# drums_01.net
KiCad netlist of a schematic drawn in EAGLE
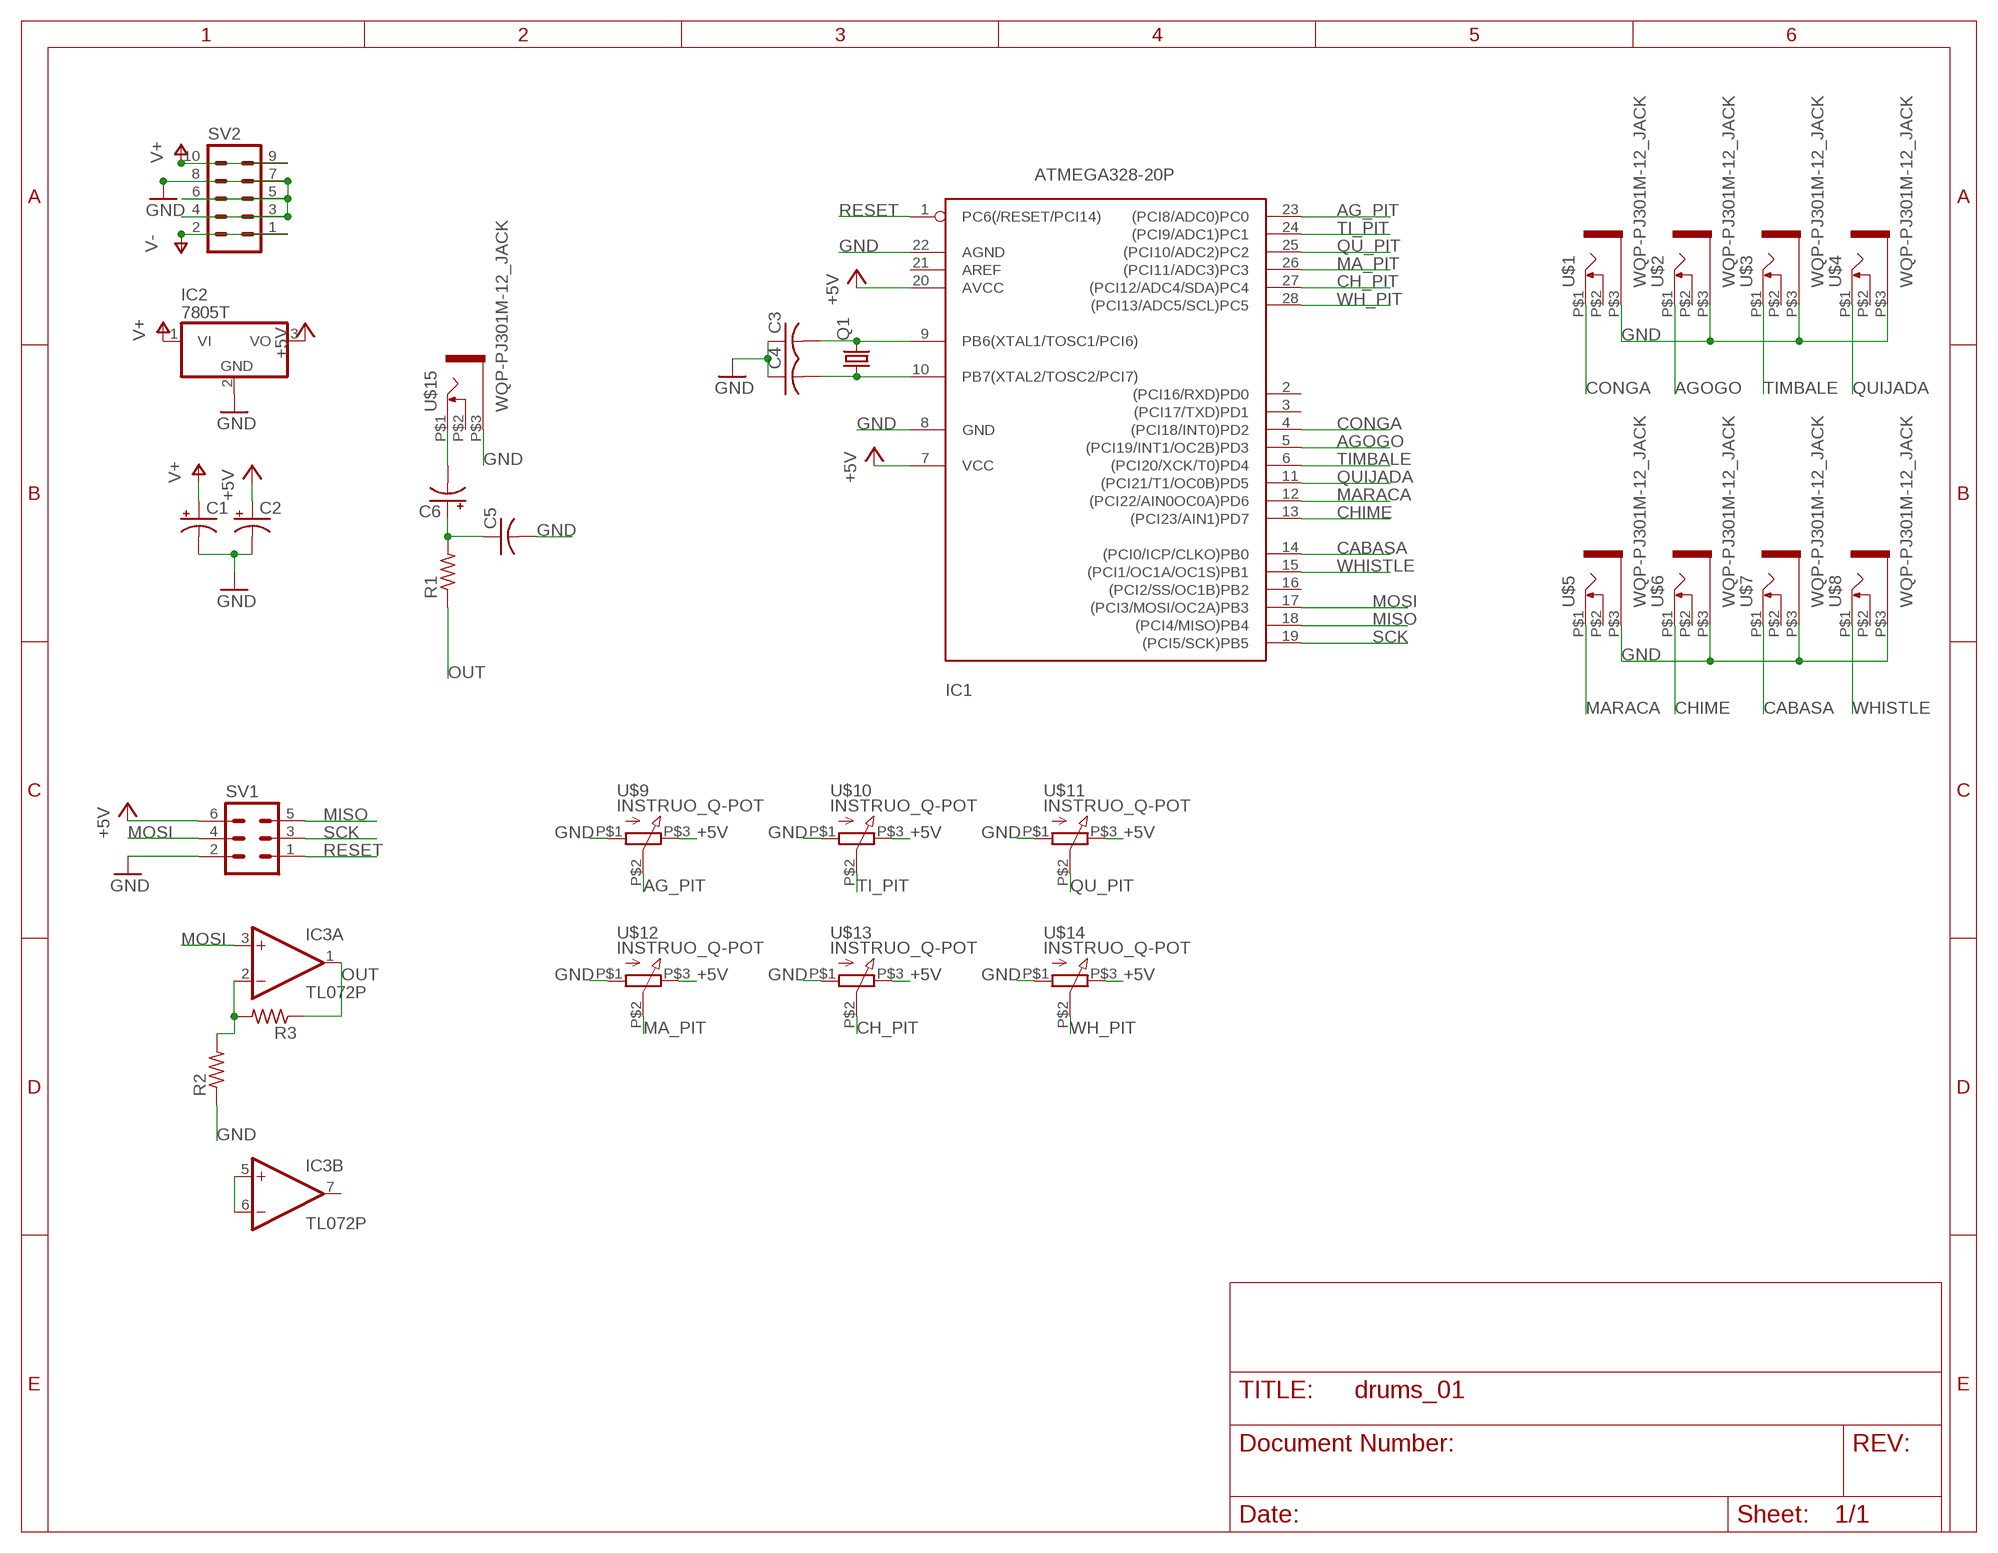
[diagram p0: schematic, sheet 1]

(export (version "E")
  (design (tool "Eeschema 10.0.6"))
  (components
    (comp (ref "C1")
      (value "CPOL-USE2.5-6")
      (footprint "eagle-import:E2,5-6")
      (libsource (lib "eagle-import") (part "CPOL-USE2.5-6"))
    )
    (comp (ref "C2")
      (value "CPOL-USE2.5-6")
      (footprint "eagle-import:E2,5-6")
      (libsource (lib "eagle-import") (part "CPOL-USE2.5-6"))
    )
    (comp (ref "C3")
      (value "C-US025-024X044")
      (footprint "eagle-import:C025-024X044")
      (libsource (lib "eagle-import") (part "C-US025-024X044"))
    )
    (comp (ref "C4")
      (value "C-US025-024X044")
      (footprint "eagle-import:C025-024X044")
      (libsource (lib "eagle-import") (part "C-US025-024X044"))
    )
    (comp (ref "C5")
      (value "C-US025-024X044")
      (footprint "eagle-import:C025-024X044")
      (libsource (lib "eagle-import") (part "C-US025-024X044"))
    )
    (comp (ref "C6")
      (value "CPOL-USE2.5-6")
      (footprint "eagle-import:E2,5-6")
      (libsource (lib "eagle-import") (part "CPOL-USE2.5-6"))
    )
    (comp (ref "IC1")
      (value "ATMEGA328-20P")
      (footprint "eagle-import:DIL28-3")
      (libsource (lib "eagle-import") (part "ATMEGA328P-20"))
    )
    (comp (ref "IC2")
      (value "7805T")
      (footprint "eagle-import:TO220H")
      (libsource (lib "eagle-import") (part "78T05"))
    )
    (comp (ref "IC3")
      (value "TL072P")
      (footprint "eagle-import:DIL08")
      (libsource (lib "eagle-import") (part "TL072P"))
    )
    (comp (ref "Q1")
      (value "CRYSTALHC49U-V")
      (footprint "eagle-import:HC49U-V")
      (libsource (lib "eagle-import") (part "CRYSTALHC49U-V"))
    )
    (comp (ref "R1")
      (value "R-US_0207/12")
      (footprint "eagle-import:0207_12")
      (libsource (lib "eagle-import") (part "R-US_0207/12"))
    )
    (comp (ref "R2")
      (value "R-US_0207/12")
      (footprint "eagle-import:0207_12")
      (libsource (lib "eagle-import") (part "R-US_0207/12"))
    )
    (comp (ref "R3")
      (value "R-US_0207/12")
      (footprint "eagle-import:0207_12")
      (libsource (lib "eagle-import") (part "R-US_0207/12"))
    )
    (comp (ref "SV1")
      (value "MA03-2")
      (footprint "eagle-import:MA03-2")
      (libsource (lib "eagle-import") (part "MA03-2"))
    )
    (comp (ref "SV2")
      (value "MA05-2")
      (footprint "eagle-import:MA05-2")
      (libsource (lib "eagle-import") (part "MA05-2"))
    )
    (comp (ref "U$1")
      (value "WQP-PJ301M-12_JACK")
      (footprint "eagle-import:WQP-PJ301M-12_JACK")
      (libsource (lib "eagle-import") (part "WQP-PJ301M-12_JACK"))
    )
    (comp (ref "U$2")
      (value "WQP-PJ301M-12_JACK")
      (footprint "eagle-import:WQP-PJ301M-12_JACK")
      (libsource (lib "eagle-import") (part "WQP-PJ301M-12_JACK"))
    )
    (comp (ref "U$3")
      (value "WQP-PJ301M-12_JACK")
      (footprint "eagle-import:WQP-PJ301M-12_JACK")
      (libsource (lib "eagle-import") (part "WQP-PJ301M-12_JACK"))
    )
    (comp (ref "U$4")
      (value "WQP-PJ301M-12_JACK")
      (footprint "eagle-import:WQP-PJ301M-12_JACK")
      (libsource (lib "eagle-import") (part "WQP-PJ301M-12_JACK"))
    )
    (comp (ref "U$5")
      (value "WQP-PJ301M-12_JACK")
      (footprint "eagle-import:WQP-PJ301M-12_JACK")
      (libsource (lib "eagle-import") (part "WQP-PJ301M-12_JACK"))
    )
    (comp (ref "U$6")
      (value "WQP-PJ301M-12_JACK")
      (footprint "eagle-import:WQP-PJ301M-12_JACK")
      (libsource (lib "eagle-import") (part "WQP-PJ301M-12_JACK"))
    )
    (comp (ref "U$7")
      (value "WQP-PJ301M-12_JACK")
      (footprint "eagle-import:WQP-PJ301M-12_JACK")
      (libsource (lib "eagle-import") (part "WQP-PJ301M-12_JACK"))
    )
    (comp (ref "U$8")
      (value "WQP-PJ301M-12_JACK")
      (footprint "eagle-import:WQP-PJ301M-12_JACK")
      (libsource (lib "eagle-import") (part "WQP-PJ301M-12_JACK"))
    )
    (comp (ref "U$9")
      (value "INSTRUO_Q-POT")
      (footprint "eagle-import:INSTRUO_Q-POT")
      (libsource (lib "eagle-import") (part "INSTRUO_Q-POT"))
    )
    (comp (ref "U$10")
      (value "INSTRUO_Q-POT")
      (footprint "eagle-import:INSTRUO_Q-POT")
      (libsource (lib "eagle-import") (part "INSTRUO_Q-POT"))
    )
    (comp (ref "U$11")
      (value "INSTRUO_Q-POT")
      (footprint "eagle-import:INSTRUO_Q-POT")
      (libsource (lib "eagle-import") (part "INSTRUO_Q-POT"))
    )
    (comp (ref "U$12")
      (value "INSTRUO_Q-POT")
      (footprint "eagle-import:INSTRUO_Q-POT")
      (libsource (lib "eagle-import") (part "INSTRUO_Q-POT"))
    )
    (comp (ref "U$13")
      (value "INSTRUO_Q-POT")
      (footprint "eagle-import:INSTRUO_Q-POT")
      (libsource (lib "eagle-import") (part "INSTRUO_Q-POT"))
    )
    (comp (ref "U$14")
      (value "INSTRUO_Q-POT")
      (footprint "eagle-import:INSTRUO_Q-POT")
      (libsource (lib "eagle-import") (part "INSTRUO_Q-POT"))
    )
    (comp (ref "U$15")
      (value "WQP-PJ301M-12_JACK")
      (footprint "eagle-import:WQP-PJ301M-12_JACK")
      (libsource (lib "eagle-import") (part "WQP-PJ301M-12_JACK"))
    )
  )
  (nets
    (net (code "1") (name "+5V") (class "Default")
      (node (ref "C2") (pin "+") (pinfunction "+_+") (pintype "passive"))
      (node (ref "IC1") (pin "20") (pinfunction "AVCC_20") (pintype "bidirectional"))
      (node (ref "IC1") (pin "7") (pinfunction "VCC_7") (pintype "bidirectional"))
      (node (ref "IC2") (pin "3") (pinfunction "VO_3") (pintype "passive"))
      (node (ref "SV1") (pin "6") (pinfunction "6_6") (pintype "passive"))
      (node (ref "U$10") (pin "P$3") (pinfunction "3_P$3") (pintype "passive"))
      (node (ref "U$11") (pin "P$3") (pinfunction "3_P$3") (pintype "passive"))
      (node (ref "U$12") (pin "P$3") (pinfunction "3_P$3") (pintype "passive"))
      (node (ref "U$13") (pin "P$3") (pinfunction "3_P$3") (pintype "passive"))
      (node (ref "U$14") (pin "P$3") (pinfunction "3_P$3") (pintype "passive"))
      (node (ref "U$9") (pin "P$3") (pinfunction "3_P$3") (pintype "passive"))
    )
    (net (code "2") (name "/AGOGO") (class "Default")
      (node (ref "IC1") (pin "5") (pinfunction "(PCI19/INT1/OC2B)PD3_5") (pintype "bidirectional"))
      (node (ref "U$2") (pin "P$1") (pinfunction "2_P$1") (pintype "passive"))
    )
    (net (code "3") (name "/AG_PIT") (class "Default")
      (node (ref "IC1") (pin "23") (pinfunction "(PCI8/ADC0)PC0_23") (pintype "bidirectional"))
      (node (ref "U$9") (pin "P$2") (pinfunction "2_P$2") (pintype "passive"))
    )
    (net (code "4") (name "/CABASA") (class "Default")
      (node (ref "IC1") (pin "14") (pinfunction "(PCI0/ICP/CLKO)PB0_14") (pintype "bidirectional"))
      (node (ref "U$7") (pin "P$1") (pinfunction "2_P$1") (pintype "passive"))
    )
    (net (code "5") (name "/CHIME") (class "Default")
      (node (ref "IC1") (pin "13") (pinfunction "(PCI23/AIN1)PD7_13") (pintype "bidirectional"))
      (node (ref "U$6") (pin "P$1") (pinfunction "2_P$1") (pintype "passive"))
    )
    (net (code "6") (name "/CH_PIT") (class "Default")
      (node (ref "IC1") (pin "27") (pinfunction "(PCI12/ADC4/SDA)PC4_27") (pintype "bidirectional"))
      (node (ref "U$13") (pin "P$2") (pinfunction "2_P$2") (pintype "passive"))
    )
    (net (code "7") (name "/CONGA") (class "Default")
      (node (ref "IC1") (pin "4") (pinfunction "(PCI18/INT0)PD2_4") (pintype "bidirectional"))
      (node (ref "U$1") (pin "P$1") (pinfunction "2_P$1") (pintype "passive"))
    )
    (net (code "8") (name "/MARACA") (class "Default")
      (node (ref "IC1") (pin "12") (pinfunction "(PCI22/AIN0OC0A)PD6_12") (pintype "bidirectional"))
      (node (ref "U$5") (pin "P$1") (pinfunction "2_P$1") (pintype "passive"))
    )
    (net (code "9") (name "/MA_PIT") (class "Default")
      (node (ref "IC1") (pin "26") (pinfunction "(PCI11/ADC3)PC3_26") (pintype "bidirectional"))
      (node (ref "U$12") (pin "P$2") (pinfunction "2_P$2") (pintype "passive"))
    )
    (net (code "10") (name "/MISO") (class "Default")
      (node (ref "IC1") (pin "18") (pinfunction "(PCI4/MISO)PB4_18") (pintype "bidirectional"))
      (node (ref "SV1") (pin "5") (pinfunction "5_5") (pintype "passive"))
    )
    (net (code "11") (name "/MOSI") (class "Default")
      (node (ref "IC1") (pin "17") (pinfunction "(PCI3/MOSI/OC2A)PB3_17") (pintype "bidirectional"))
      (node (ref "IC3") (pin "3") (pinfunction "+IN_3") (pintype "input"))
      (node (ref "SV1") (pin "4") (pinfunction "4_4") (pintype "passive"))
    )
    (net (code "12") (name "/OUT") (class "Default")
      (node (ref "IC3") (pin "1") (pinfunction "OUT_1") (pintype "output"))
      (node (ref "R1") (pin "1") (pinfunction "1_1") (pintype "passive"))
      (node (ref "R3") (pin "1") (pinfunction "1_1") (pintype "passive"))
    )
    (net (code "13") (name "/QUIJADA") (class "Default")
      (node (ref "IC1") (pin "11") (pinfunction "(PCI21/T1/OC0B)PD5_11") (pintype "bidirectional"))
      (node (ref "U$4") (pin "P$1") (pinfunction "2_P$1") (pintype "passive"))
    )
    (net (code "14") (name "/QU_PIT") (class "Default")
      (node (ref "IC1") (pin "25") (pinfunction "(PCI10/ADC2)PC2_25") (pintype "bidirectional"))
      (node (ref "U$11") (pin "P$2") (pinfunction "2_P$2") (pintype "passive"))
    )
    (net (code "15") (name "/RESET") (class "Default")
      (node (ref "IC1") (pin "1") (pinfunction "PC6(/RESET/PCI14)_1") (pintype "bidirectional"))
      (node (ref "SV1") (pin "1") (pinfunction "1_1") (pintype "passive"))
    )
    (net (code "16") (name "/SCK") (class "Default")
      (node (ref "IC1") (pin "19") (pinfunction "(PCI5/SCK)PB5_19") (pintype "bidirectional"))
      (node (ref "SV1") (pin "3") (pinfunction "3_3") (pintype "passive"))
    )
    (net (code "17") (name "/TIMBALE") (class "Default")
      (node (ref "IC1") (pin "6") (pinfunction "(PCI20/XCK/T0)PD4_6") (pintype "bidirectional"))
      (node (ref "U$3") (pin "P$1") (pinfunction "2_P$1") (pintype "passive"))
    )
    (net (code "18") (name "/TI_PIT") (class "Default")
      (node (ref "IC1") (pin "24") (pinfunction "(PCI9/ADC1)PC1_24") (pintype "bidirectional"))
      (node (ref "U$10") (pin "P$2") (pinfunction "2_P$2") (pintype "passive"))
    )
    (net (code "19") (name "/WHISTLE") (class "Default")
      (node (ref "IC1") (pin "15") (pinfunction "(PCI1/OC1A/OC1S)PB1_15") (pintype "bidirectional"))
      (node (ref "U$8") (pin "P$1") (pinfunction "2_P$1") (pintype "passive"))
    )
    (net (code "20") (name "/WH_PIT") (class "Default")
      (node (ref "IC1") (pin "28") (pinfunction "(PCI13/ADC5/SCL)PC5_28") (pintype "bidirectional"))
      (node (ref "U$14") (pin "P$2") (pinfunction "2_P$2") (pintype "passive"))
    )
    (net (code "21") (name "GND") (class "Default")
      (node (ref "C1") (pin "-") (pinfunction "-_-") (pintype "passive"))
      (node (ref "C2") (pin "-") (pinfunction "-_-") (pintype "passive"))
      (node (ref "C3") (pin "1") (pinfunction "1_1") (pintype "passive"))
      (node (ref "C4") (pin "1") (pinfunction "1_1") (pintype "passive"))
      (node (ref "C5") (pin "2") (pinfunction "2_2") (pintype "passive"))
      (node (ref "IC1") (pin "22") (pinfunction "AGND_22") (pintype "bidirectional"))
      (node (ref "IC1") (pin "8") (pinfunction "GND_8") (pintype "bidirectional"))
      (node (ref "IC2") (pin "2") (pinfunction "GND_2") (pintype "passive"))
      (node (ref "R2") (pin "1") (pinfunction "1_1") (pintype "passive"))
      (node (ref "SV1") (pin "2") (pinfunction "2_2") (pintype "passive"))
      (node (ref "SV2") (pin "3") (pinfunction "3_3") (pintype "passive"))
      (node (ref "SV2") (pin "4") (pinfunction "4_4") (pintype "passive"))
      (node (ref "SV2") (pin "5") (pinfunction "5_5") (pintype "passive"))
      (node (ref "SV2") (pin "6") (pinfunction "6_6") (pintype "passive"))
      (node (ref "SV2") (pin "7") (pinfunction "7_7") (pintype "passive"))
      (node (ref "SV2") (pin "8") (pinfunction "8_8") (pintype "passive"))
      (node (ref "U$1") (pin "P$3") (pinfunction "1_P$3") (pintype "passive"))
      (node (ref "U$10") (pin "P$1") (pinfunction "1_P$1") (pintype "passive"))
      (node (ref "U$11") (pin "P$1") (pinfunction "1_P$1") (pintype "passive"))
      (node (ref "U$12") (pin "P$1") (pinfunction "1_P$1") (pintype "passive"))
      (node (ref "U$13") (pin "P$1") (pinfunction "1_P$1") (pintype "passive"))
      (node (ref "U$14") (pin "P$1") (pinfunction "1_P$1") (pintype "passive"))
      (node (ref "U$15") (pin "P$3") (pinfunction "1_P$3") (pintype "passive"))
      (node (ref "U$2") (pin "P$3") (pinfunction "1_P$3") (pintype "passive"))
      (node (ref "U$3") (pin "P$3") (pinfunction "1_P$3") (pintype "passive"))
      (node (ref "U$4") (pin "P$3") (pinfunction "1_P$3") (pintype "passive"))
      (node (ref "U$5") (pin "P$3") (pinfunction "1_P$3") (pintype "passive"))
      (node (ref "U$6") (pin "P$3") (pinfunction "1_P$3") (pintype "passive"))
      (node (ref "U$7") (pin "P$3") (pinfunction "1_P$3") (pintype "passive"))
      (node (ref "U$8") (pin "P$3") (pinfunction "1_P$3") (pintype "passive"))
      (node (ref "U$9") (pin "P$1") (pinfunction "1_P$1") (pintype "passive"))
    )
    (net (code "22") (name "Net-(C5-Pad1)") (class "Default")
      (node (ref "C5") (pin "1") (pinfunction "1_1") (pintype "passive"))
      (node (ref "C6") (pin "+") (pinfunction "+_+") (pintype "passive"))
      (node (ref "R1") (pin "2") (pinfunction "2_2") (pintype "passive"))
    )
    (net (code "23") (name "Net-(IC1-PB6(XTAL1{slash}TOSC1{slash}PCI6))") (class "Default")
      (node (ref "C3") (pin "2") (pinfunction "2_2") (pintype "passive"))
      (node (ref "IC1") (pin "9") (pinfunction "PB6(XTAL1/TOSC1/PCI6)_9") (pintype "bidirectional"))
      (node (ref "Q1") (pin "2") (pinfunction "2_2") (pintype "passive"))
    )
    (net (code "24") (name "Net-(IC1-PB7(XTAL2{slash}TOSC2{slash}PCI7))") (class "Default")
      (node (ref "C4") (pin "2") (pinfunction "2_2") (pintype "passive"))
      (node (ref "IC1") (pin "10") (pinfunction "PB7(XTAL2/TOSC2/PCI7)_10") (pintype "bidirectional"))
      (node (ref "Q1") (pin "1") (pinfunction "1_1") (pintype "passive"))
    )
    (net (code "25") (name "Net-(IC3A--IN)") (class "Default")
      (node (ref "IC3") (pin "2") (pinfunction "-IN_2") (pintype "input"))
      (node (ref "R2") (pin "2") (pinfunction "2_2") (pintype "passive"))
      (node (ref "R3") (pin "2") (pinfunction "2_2") (pintype "passive"))
    )
    (net (code "26") (name "Net-(IC3B-+IN)") (class "Default")
      (node (ref "IC3") (pin "5") (pinfunction "+IN_5") (pintype "input"))
      (node (ref "IC3") (pin "6") (pinfunction "-IN_6") (pintype "input"))
    )
    (net (code "27") (name "Net-(U$15-2)") (class "Default")
      (node (ref "C6") (pin "-") (pinfunction "-_-") (pintype "passive"))
      (node (ref "U$15") (pin "P$1") (pinfunction "2_P$1") (pintype "passive"))
    )
    (net (code "28") (name "V+") (class "Default")
      (node (ref "C1") (pin "+") (pinfunction "+_+") (pintype "passive"))
      (node (ref "IC2") (pin "1") (pinfunction "VI_1") (pintype "input"))
      (node (ref "SV2") (pin "10") (pinfunction "10_10") (pintype "passive"))
      (node (ref "SV2") (pin "9") (pinfunction "9_9") (pintype "passive"))
    )
    (net (code "29") (name "V-") (class "Default")
      (node (ref "SV2") (pin "1") (pinfunction "1_1") (pintype "passive"))
      (node (ref "SV2") (pin "2") (pinfunction "2_2") (pintype "passive"))
    )
    (net (code "30") (name "unconnected-(IC1-(PCI2{slash}SS{slash}OC1B)PB2-Pad16)") (class "Default")
      (node (ref "IC1") (pin "16") (pinfunction "(PCI2/SS/OC1B)PB2_16") (pintype "bidirectional"))
    )
    (net (code "31") (name "unconnected-(IC1-(PCI16{slash}RXD)PD0-Pad2)") (class "Default")
      (node (ref "IC1") (pin "2") (pinfunction "(PCI16/RXD)PD0_2") (pintype "bidirectional"))
    )
    (net (code "32") (name "unconnected-(IC1-(PCI17{slash}TXD)PD1-Pad3)") (class "Default")
      (node (ref "IC1") (pin "3") (pinfunction "(PCI17/TXD)PD1_3") (pintype "bidirectional"))
    )
    (net (code "33") (name "unconnected-(IC1-AREF-Pad21)") (class "Default")
      (node (ref "IC1") (pin "21") (pinfunction "AREF_21") (pintype "bidirectional"))
    )
    (net (code "34") (name "unconnected-(IC3B-OUT-Pad7)") (class "Default")
      (node (ref "IC3") (pin "7") (pinfunction "OUT_7") (pintype "output"))
    )
    (net (code "35") (name "unconnected-(U$1-3-PadP$2)") (class "Default")
      (node (ref "U$1") (pin "P$2") (pinfunction "3_P$2") (pintype "passive"))
    )
    (net (code "36") (name "unconnected-(U$2-3-PadP$2)") (class "Default")
      (node (ref "U$2") (pin "P$2") (pinfunction "3_P$2") (pintype "passive"))
    )
    (net (code "37") (name "unconnected-(U$3-3-PadP$2)") (class "Default")
      (node (ref "U$3") (pin "P$2") (pinfunction "3_P$2") (pintype "passive"))
    )
    (net (code "38") (name "unconnected-(U$4-3-PadP$2)") (class "Default")
      (node (ref "U$4") (pin "P$2") (pinfunction "3_P$2") (pintype "passive"))
    )
    (net (code "39") (name "unconnected-(U$5-3-PadP$2)") (class "Default")
      (node (ref "U$5") (pin "P$2") (pinfunction "3_P$2") (pintype "passive"))
    )
    (net (code "40") (name "unconnected-(U$6-3-PadP$2)") (class "Default")
      (node (ref "U$6") (pin "P$2") (pinfunction "3_P$2") (pintype "passive"))
    )
    (net (code "41") (name "unconnected-(U$7-3-PadP$2)") (class "Default")
      (node (ref "U$7") (pin "P$2") (pinfunction "3_P$2") (pintype "passive"))
    )
    (net (code "42") (name "unconnected-(U$8-3-PadP$2)") (class "Default")
      (node (ref "U$8") (pin "P$2") (pinfunction "3_P$2") (pintype "passive"))
    )
    (net (code "43") (name "unconnected-(U$15-3-PadP$2)") (class "Default")
      (node (ref "U$15") (pin "P$2") (pinfunction "3_P$2") (pintype "passive"))
    )
  )
)
